# P_ytka.net
KiCad netlist of a schematic drawn in EAGLE
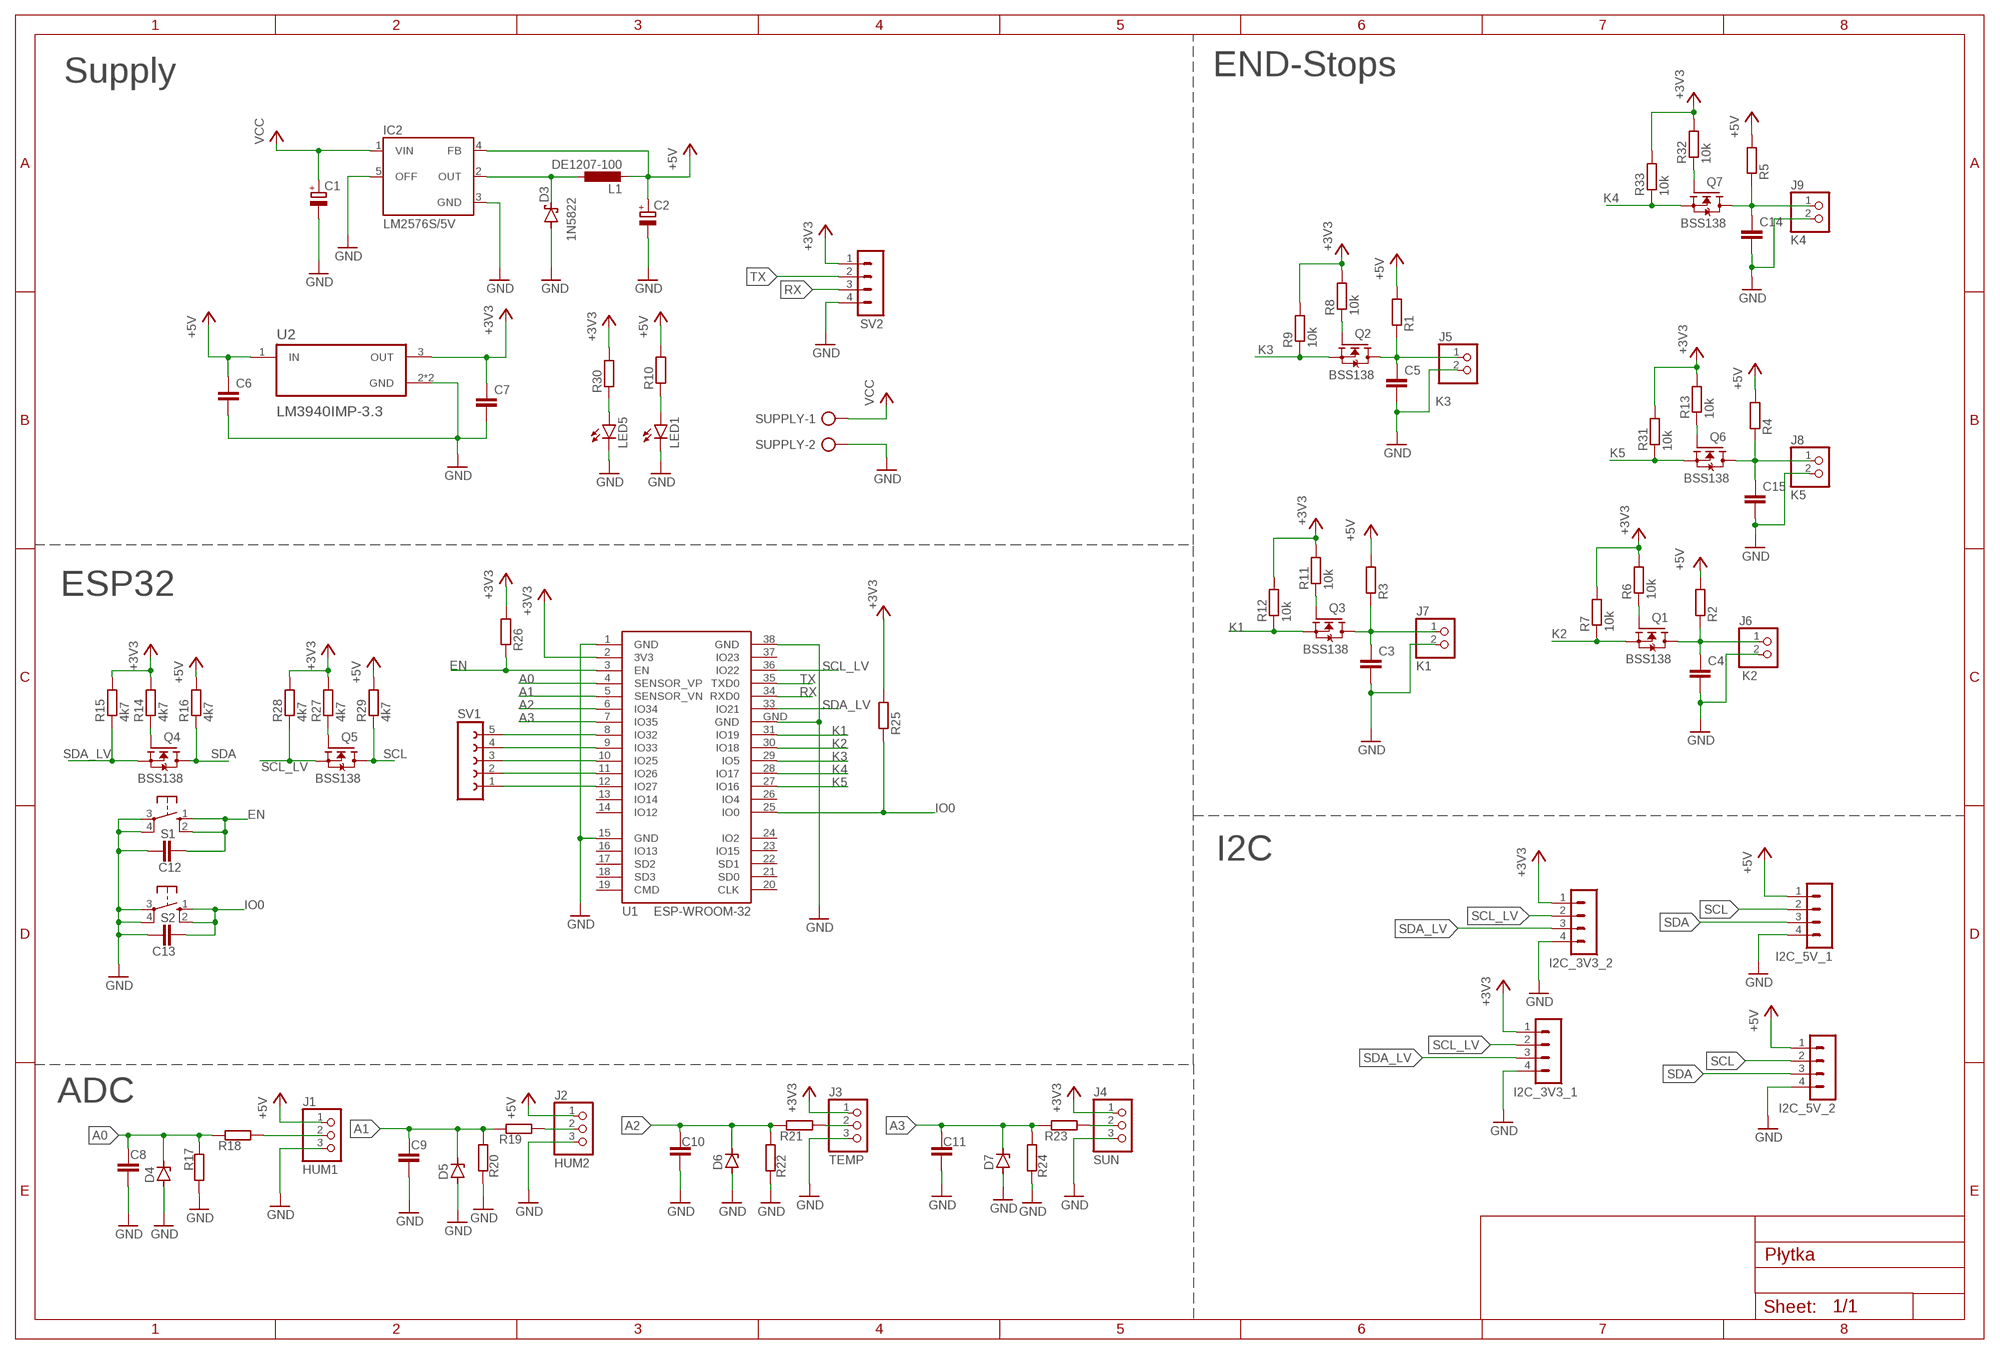
[diagram p0: schematic, sheet 1]

(export (version "E")
  (design (tool "Eeschema 10.0.6"))
  (components
    (comp (ref "C1")
      (value "CPOL-EUE2.5-6")
      (footprint "eagle-import:E2,5-6")
      (libsource (lib "eagle-import") (part "CPOL-EUE2.5-6"))
    )
    (comp (ref "C2")
      (value "CPOL-EUE3.5-8")
      (footprint "eagle-import:E3,5-8")
      (libsource (lib "eagle-import") (part "CPOL-EUE3.5-8"))
    )
    (comp (ref "C3")
      (value "C-EUC0805K")
      (footprint "eagle-import:C0805K")
      (libsource (lib "eagle-import") (part "C-EUC0805K"))
    )
    (comp (ref "C4")
      (value "C-EUC0805K")
      (footprint "eagle-import:C0805K")
      (libsource (lib "eagle-import") (part "C-EUC0805K"))
    )
    (comp (ref "C5")
      (value "C-EUC0805K")
      (footprint "eagle-import:C0805K")
      (libsource (lib "eagle-import") (part "C-EUC0805K"))
    )
    (comp (ref "C6")
      (value "C-EUC0805K")
      (footprint "eagle-import:C0805K")
      (libsource (lib "eagle-import") (part "C-EUC0805K"))
    )
    (comp (ref "C7")
      (value "C-EUC0805K")
      (footprint "eagle-import:C0805K")
      (libsource (lib "eagle-import") (part "C-EUC0805K"))
    )
    (comp (ref "C8")
      (value "C-EUC0805K")
      (footprint "eagle-import:C0805K")
      (libsource (lib "eagle-import") (part "C-EUC0805K"))
    )
    (comp (ref "C9")
      (value "C-EUC0805K")
      (footprint "eagle-import:C0805K")
      (libsource (lib "eagle-import") (part "C-EUC0805K"))
    )
    (comp (ref "C10")
      (value "C-EUC0805K")
      (footprint "eagle-import:C0805K")
      (libsource (lib "eagle-import") (part "C-EUC0805K"))
    )
    (comp (ref "C11")
      (value "C-EUC0805K")
      (footprint "eagle-import:C0805K")
      (libsource (lib "eagle-import") (part "C-EUC0805K"))
    )
    (comp (ref "C12")
      (value "C-EUC0805K")
      (footprint "eagle-import:C0805K")
      (libsource (lib "eagle-import") (part "C-EUC0805K"))
    )
    (comp (ref "C13")
      (value "C-EUC0805K")
      (footprint "eagle-import:C0805K")
      (libsource (lib "eagle-import") (part "C-EUC0805K"))
    )
    (comp (ref "C14")
      (value "C-EUC0805K")
      (footprint "eagle-import:C0805K")
      (libsource (lib "eagle-import") (part "C-EUC0805K"))
    )
    (comp (ref "C15")
      (value "C-EUC0805K")
      (footprint "eagle-import:C0805K")
      (libsource (lib "eagle-import") (part "C-EUC0805K"))
    )
    (comp (ref "D3")
      (value "1N5822")
      (footprint "eagle-import:C4111-15")
      (libsource (lib "eagle-import") (part "1N5908"))
    )
    (comp (ref "D4")
      (value "ZENER-DIODESOD80C")
      (footprint "eagle-import:SOD80C")
      (libsource (lib "eagle-import") (part "ZENER-DIODESOD80C"))
    )
    (comp (ref "D5")
      (value "ZENER-DIODESOD80C")
      (footprint "eagle-import:SOD80C")
      (libsource (lib "eagle-import") (part "ZENER-DIODESOD80C"))
    )
    (comp (ref "D6")
      (value "ZENER-DIODESOD80C")
      (footprint "eagle-import:SOD80C")
      (libsource (lib "eagle-import") (part "ZENER-DIODESOD80C"))
    )
    (comp (ref "D7")
      (value "ZENER-DIODESOD80C")
      (footprint "eagle-import:SOD80C")
      (libsource (lib "eagle-import") (part "ZENER-DIODESOD80C"))
    )
    (comp (ref "I2C_3V3_1")
      (value "MA04-1")
      (footprint "eagle-import:MA04-1")
      (libsource (lib "eagle-import") (part "MA04-1"))
    )
    (comp (ref "I2C_3V3_2")
      (value "MA04-1")
      (footprint "eagle-import:MA04-1")
      (libsource (lib "eagle-import") (part "MA04-1"))
    )
    (comp (ref "I2C_5V_1")
      (value "MA04-1")
      (footprint "eagle-import:MA04-1")
      (libsource (lib "eagle-import") (part "MA04-1"))
    )
    (comp (ref "I2C_5V_2")
      (value "MA04-1")
      (footprint "eagle-import:MA04-1")
      (libsource (lib "eagle-import") (part "MA04-1"))
    )
    (comp (ref "IC2")
      (value "LM2576S/5V")
      (footprint "eagle-import:TO220-5")
      (libsource (lib "eagle-import") (part "LM2576T"))
    )
    (comp (ref "J1")
      (value "HUM1")
      (footprint "eagle-import:W_TYPE_2MM_3_N")
      (libsource (lib "eagle-import") (part "WT-2MM-3PINSTRAIGHT"))
    )
    (comp (ref "J2")
      (value "HUM2")
      (footprint "eagle-import:W_TYPE_2MM_3_N")
      (libsource (lib "eagle-import") (part "WT-2MM-3PINSTRAIGHT"))
    )
    (comp (ref "J3")
      (value "TEMP")
      (footprint "eagle-import:W_TYPE_2MM_3_N")
      (libsource (lib "eagle-import") (part "WT-2MM-3PINSTRAIGHT"))
    )
    (comp (ref "J4")
      (value "SUN")
      (footprint "eagle-import:W_TYPE_2MM_3_N")
      (libsource (lib "eagle-import") (part "WT-2MM-3PINSTRAIGHT"))
    )
    (comp (ref "J5")
      (value "K3")
      (footprint "eagle-import:W_TYPE_2MM_2_N")
      (libsource (lib "eagle-import") (part "WT-2MM-2PINSTRAIGHT"))
    )
    (comp (ref "J6")
      (value "K2")
      (footprint "eagle-import:W_TYPE_2MM_2_N")
      (libsource (lib "eagle-import") (part "WT-2MM-2PINSTRAIGHT"))
    )
    (comp (ref "J7")
      (value "K1")
      (footprint "eagle-import:W_TYPE_2MM_2_N")
      (libsource (lib "eagle-import") (part "WT-2MM-2PINSTRAIGHT"))
    )
    (comp (ref "J8")
      (value "K5")
      (footprint "eagle-import:W_TYPE_2MM_2_N")
      (libsource (lib "eagle-import") (part "WT-2MM-2PINSTRAIGHT"))
    )
    (comp (ref "J9")
      (value "K4")
      (footprint "eagle-import:W_TYPE_2MM_2_N")
      (libsource (lib "eagle-import") (part "WT-2MM-2PINSTRAIGHT"))
    )
    (comp (ref "L1")
      (value "DE1207-100")
      (footprint "eagle-import:DE1207")
      (libsource (lib "eagle-import") (part "DE1207-100"))
    )
    (comp (ref "LED1")
      (value "LEDSML0805")
      (footprint "eagle-import:SML0805")
      (libsource (lib "eagle-import") (part "LEDSML0805"))
    )
    (comp (ref "LED5")
      (value "LEDSML0805")
      (footprint "eagle-import:SML0805")
      (libsource (lib "eagle-import") (part "LEDSML0805"))
    )
    (comp (ref "Q1")
      (value "BSS138")
      (footprint "eagle-import:SOT23")
      (fields (field (name "MF") "Fairchild"))
      (libsource (lib "eagle-import") (part "BSS138"))
    )
    (comp (ref "Q2")
      (value "BSS138")
      (footprint "eagle-import:SOT23")
      (fields (field (name "MF") "Fairchild"))
      (libsource (lib "eagle-import") (part "BSS138"))
    )
    (comp (ref "Q3")
      (value "BSS138")
      (footprint "eagle-import:SOT23")
      (fields (field (name "MF") "Fairchild"))
      (libsource (lib "eagle-import") (part "BSS138"))
    )
    (comp (ref "Q4")
      (value "BSS138")
      (footprint "eagle-import:SOT23")
      (fields (field (name "MF") "Fairchild"))
      (libsource (lib "eagle-import") (part "BSS138"))
    )
    (comp (ref "Q5")
      (value "BSS138")
      (footprint "eagle-import:SOT23")
      (fields (field (name "MF") "Fairchild"))
      (libsource (lib "eagle-import") (part "BSS138"))
    )
    (comp (ref "Q6")
      (value "BSS138")
      (footprint "eagle-import:SOT23")
      (fields (field (name "MF") "Fairchild"))
      (libsource (lib "eagle-import") (part "BSS138"))
    )
    (comp (ref "Q7")
      (value "BSS138")
      (footprint "eagle-import:SOT23")
      (fields (field (name "MF") "Fairchild"))
      (libsource (lib "eagle-import") (part "BSS138"))
    )
    (comp (ref "R1")
      (value "R-EU_R0805")
      (footprint "eagle-import:R0805")
      (libsource (lib "eagle-import") (part "R-EU_R0805"))
    )
    (comp (ref "R2")
      (value "R-EU_R0805")
      (footprint "eagle-import:R0805")
      (libsource (lib "eagle-import") (part "R-EU_R0805"))
    )
    (comp (ref "R3")
      (value "R-EU_R0805")
      (footprint "eagle-import:R0805")
      (libsource (lib "eagle-import") (part "R-EU_R0805"))
    )
    (comp (ref "R4")
      (value "R-EU_R0805")
      (footprint "eagle-import:R0805")
      (libsource (lib "eagle-import") (part "R-EU_R0805"))
    )
    (comp (ref "R5")
      (value "R-EU_R0805")
      (footprint "eagle-import:R0805")
      (libsource (lib "eagle-import") (part "R-EU_R0805"))
    )
    (comp (ref "R6")
      (value "10k")
      (footprint "eagle-import:R0805")
      (libsource (lib "eagle-import") (part "R-EU_R0805"))
    )
    (comp (ref "R7")
      (value "10k")
      (footprint "eagle-import:R0805")
      (libsource (lib "eagle-import") (part "R-EU_R0805"))
    )
    (comp (ref "R8")
      (value "10k")
      (footprint "eagle-import:R0805")
      (libsource (lib "eagle-import") (part "R-EU_R0805"))
    )
    (comp (ref "R9")
      (value "10k")
      (footprint "eagle-import:R0805")
      (libsource (lib "eagle-import") (part "R-EU_R0805"))
    )
    (comp (ref "R10")
      (value "R-EU_R0805")
      (footprint "eagle-import:R0805")
      (libsource (lib "eagle-import") (part "R-EU_R0805"))
    )
    (comp (ref "R11")
      (value "10k")
      (footprint "eagle-import:R0805")
      (libsource (lib "eagle-import") (part "R-EU_R0805"))
    )
    (comp (ref "R12")
      (value "10k")
      (footprint "eagle-import:R0805")
      (libsource (lib "eagle-import") (part "R-EU_R0805"))
    )
    (comp (ref "R13")
      (value "10k")
      (footprint "eagle-import:R0805")
      (libsource (lib "eagle-import") (part "R-EU_R0805"))
    )
    (comp (ref "R14")
      (value "4k7")
      (footprint "eagle-import:R0805")
      (libsource (lib "eagle-import") (part "R-EU_R0805"))
    )
    (comp (ref "R15")
      (value "4k7")
      (footprint "eagle-import:R0805")
      (libsource (lib "eagle-import") (part "R-EU_R0805"))
    )
    (comp (ref "R16")
      (value "4k7")
      (footprint "eagle-import:R0805")
      (libsource (lib "eagle-import") (part "R-EU_R0805"))
    )
    (comp (ref "R17")
      (value "R-EU_R0805")
      (footprint "eagle-import:R0805")
      (libsource (lib "eagle-import") (part "R-EU_R0805"))
    )
    (comp (ref "R18")
      (value "R-EU_R0805")
      (footprint "eagle-import:R0805")
      (libsource (lib "eagle-import") (part "R-EU_R0805"))
    )
    (comp (ref "R19")
      (value "R-EU_R0805")
      (footprint "eagle-import:R0805")
      (libsource (lib "eagle-import") (part "R-EU_R0805"))
    )
    (comp (ref "R20")
      (value "R-EU_R0805")
      (footprint "eagle-import:R0805")
      (libsource (lib "eagle-import") (part "R-EU_R0805"))
    )
    (comp (ref "R21")
      (value "R-EU_R0805")
      (footprint "eagle-import:R0805")
      (libsource (lib "eagle-import") (part "R-EU_R0805"))
    )
    (comp (ref "R22")
      (value "R-EU_R0805")
      (footprint "eagle-import:R0805")
      (libsource (lib "eagle-import") (part "R-EU_R0805"))
    )
    (comp (ref "R23")
      (value "R-EU_R0805")
      (footprint "eagle-import:R0805")
      (libsource (lib "eagle-import") (part "R-EU_R0805"))
    )
    (comp (ref "R24")
      (value "R-EU_R0805")
      (footprint "eagle-import:R0805")
      (libsource (lib "eagle-import") (part "R-EU_R0805"))
    )
    (comp (ref "R25")
      (value "R-EU_R0805")
      (footprint "eagle-import:R0805")
      (libsource (lib "eagle-import") (part "R-EU_R0805"))
    )
    (comp (ref "R26")
      (value "R-EU_R0805")
      (footprint "eagle-import:R0805")
      (libsource (lib "eagle-import") (part "R-EU_R0805"))
    )
    (comp (ref "R27")
      (value "4k7")
      (footprint "eagle-import:R0805")
      (libsource (lib "eagle-import") (part "R-EU_R0805"))
    )
    (comp (ref "R28")
      (value "4k7")
      (footprint "eagle-import:R0805")
      (libsource (lib "eagle-import") (part "R-EU_R0805"))
    )
    (comp (ref "R29")
      (value "4k7")
      (footprint "eagle-import:R0805")
      (libsource (lib "eagle-import") (part "R-EU_R0805"))
    )
    (comp (ref "R30")
      (value "R-EU_R0805")
      (footprint "eagle-import:R0805")
      (libsource (lib "eagle-import") (part "R-EU_R0805"))
    )
    (comp (ref "R31")
      (value "10k")
      (footprint "eagle-import:R0805")
      (libsource (lib "eagle-import") (part "R-EU_R0805"))
    )
    (comp (ref "R32")
      (value "10k")
      (footprint "eagle-import:R0805")
      (libsource (lib "eagle-import") (part "R-EU_R0805"))
    )
    (comp (ref "R33")
      (value "10k")
      (footprint "eagle-import:R0805")
      (libsource (lib "eagle-import") (part "R-EU_R0805"))
    )
    (comp (ref "S1")
      (value "10-XX")
      (footprint "eagle-import:B3F-10XX")
      (fields (field (name "MPN") "B3F-1000"))
      (libsource (lib "eagle-import") (part "10-XX"))
    )
    (comp (ref "S2")
      (value "10-XX")
      (footprint "eagle-import:B3F-10XX")
      (fields (field (name "MPN") "B3F-1000"))
      (libsource (lib "eagle-import") (part "10-XX"))
    )
    (comp (ref "SUPPLY")
      (value "AK500/2-H")
      (footprint "eagle-import:AK500_2-H")
      (libsource (lib "eagle-import") (part "AK500/2-H"))
    )
    (comp (ref "SV1")
      (value "FE05-1")
      (footprint "eagle-import:FE05-1")
      (libsource (lib "eagle-import") (part "FE05-1"))
    )
    (comp (ref "SV2")
      (value "MA04-1")
      (footprint "eagle-import:MA04-1")
      (libsource (lib "eagle-import") (part "MA04-1"))
    )
    (comp (ref "U1")
      (value "ESP-WROOM-32")
      (footprint "eagle-import:ESP-WROOM-32")
      (libsource (lib "eagle-import") (part "ESP-WROOM-32"))
    )
    (comp (ref "U2")
      (value "LM3940IMP-3.3")
      (footprint "eagle-import:SOT230P700X180-4N")
      (fields (field (name "MF") "Texas Instruments"))
      (libsource (lib "eagle-import") (part "LM3940IMP-3.3"))
    )
  )
  (nets
    (net (code "1") (name "+3V3") (class "Default")
      (node (ref "C7") (pin "1") (pinfunction "1_1") (pintype "passive"))
      (node (ref "I2C_3V3_1") (pin "1") (pinfunction "1_1") (pintype "passive"))
      (node (ref "I2C_3V3_2") (pin "1") (pinfunction "1_1") (pintype "passive"))
      (node (ref "J3") (pin "1") (pinfunction "1_1") (pintype "passive"))
      (node (ref "J4") (pin "1") (pinfunction "1_1") (pintype "passive"))
      (node (ref "R11") (pin "2") (pinfunction "2_2") (pintype "passive"))
      (node (ref "R12") (pin "2") (pinfunction "2_2") (pintype "passive"))
      (node (ref "R13") (pin "2") (pinfunction "2_2") (pintype "passive"))
      (node (ref "R14") (pin "2") (pinfunction "2_2") (pintype "passive"))
      (node (ref "R15") (pin "2") (pinfunction "2_2") (pintype "passive"))
      (node (ref "R25") (pin "2") (pinfunction "2_2") (pintype "passive"))
      (node (ref "R26") (pin "2") (pinfunction "2_2") (pintype "passive"))
      (node (ref "R27") (pin "2") (pinfunction "2_2") (pintype "passive"))
      (node (ref "R28") (pin "2") (pinfunction "2_2") (pintype "passive"))
      (node (ref "R30") (pin "2") (pinfunction "2_2") (pintype "passive"))
      (node (ref "R31") (pin "2") (pinfunction "2_2") (pintype "passive"))
      (node (ref "R32") (pin "2") (pinfunction "2_2") (pintype "passive"))
      (node (ref "R33") (pin "2") (pinfunction "2_2") (pintype "passive"))
      (node (ref "R6") (pin "2") (pinfunction "2_2") (pintype "passive"))
      (node (ref "R7") (pin "2") (pinfunction "2_2") (pintype "passive"))
      (node (ref "R8") (pin "2") (pinfunction "2_2") (pintype "passive"))
      (node (ref "R9") (pin "2") (pinfunction "2_2") (pintype "passive"))
      (node (ref "SV2") (pin "1") (pinfunction "1_1") (pintype "passive"))
      (node (ref "U1") (pin "2") (pinfunction "3V3_2") (pintype "power_in"))
      (node (ref "U2") (pin "3") (pinfunction "OUT_3") (pintype "output"))
    )
    (net (code "2") (name "+5V") (class "Default")
      (node (ref "C2") (pin "+") (pinfunction "+_+") (pintype "passive"))
      (node (ref "C6") (pin "1") (pinfunction "1_1") (pintype "passive"))
      (node (ref "I2C_5V_1") (pin "1") (pinfunction "1_1") (pintype "passive"))
      (node (ref "I2C_5V_2") (pin "1") (pinfunction "1_1") (pintype "passive"))
      (node (ref "IC2") (pin "4") (pinfunction "FB_4") (pintype "input"))
      (node (ref "J1") (pin "1") (pinfunction "1_1") (pintype "passive"))
      (node (ref "J2") (pin "1") (pinfunction "1_1") (pintype "passive"))
      (node (ref "L1") (pin "2") (pinfunction "2_2") (pintype "passive"))
      (node (ref "R1") (pin "2") (pinfunction "2_2") (pintype "passive"))
      (node (ref "R10") (pin "2") (pinfunction "2_2") (pintype "passive"))
      (node (ref "R16") (pin "2") (pinfunction "2_2") (pintype "passive"))
      (node (ref "R2") (pin "2") (pinfunction "2_2") (pintype "passive"))
      (node (ref "R29") (pin "2") (pinfunction "2_2") (pintype "passive"))
      (node (ref "R3") (pin "2") (pinfunction "2_2") (pintype "passive"))
      (node (ref "R4") (pin "2") (pinfunction "2_2") (pintype "passive"))
      (node (ref "R5") (pin "2") (pinfunction "2_2") (pintype "passive"))
      (node (ref "U2") (pin "1") (pinfunction "IN_1") (pintype "input"))
    )
    (net (code "3") (name "/EN") (class "Default")
      (node (ref "C12") (pin "2") (pinfunction "2_2") (pintype "passive"))
      (node (ref "R26") (pin "1") (pinfunction "1_1") (pintype "passive"))
      (node (ref "S1") (pin "1") (pinfunction "S_1") (pintype "passive"))
      (node (ref "S1") (pin "2") (pinfunction "S1_2") (pintype "passive"))
      (node (ref "U1") (pin "3") (pinfunction "EN_3") (pintype "input"))
    )
    (net (code "4") (name "/IO0") (class "Default")
      (node (ref "C13") (pin "2") (pinfunction "2_2") (pintype "passive"))
      (node (ref "R25") (pin "1") (pinfunction "1_1") (pintype "passive"))
      (node (ref "S2") (pin "1") (pinfunction "S_1") (pintype "passive"))
      (node (ref "S2") (pin "2") (pinfunction "S1_2") (pintype "passive"))
      (node (ref "U1") (pin "25") (pinfunction "IO0_25") (pintype "bidirectional"))
    )
    (net (code "5") (name "/K1") (class "Default")
      (node (ref "Q3") (pin "2") (pinfunction "S_2") (pintype "passive"))
      (node (ref "R12") (pin "1") (pinfunction "1_1") (pintype "passive"))
      (node (ref "U1") (pin "31") (pinfunction "IO19_31") (pintype "bidirectional"))
    )
    (net (code "6") (name "/K2") (class "Default")
      (node (ref "Q1") (pin "2") (pinfunction "S_2") (pintype "passive"))
      (node (ref "R7") (pin "1") (pinfunction "1_1") (pintype "passive"))
      (node (ref "U1") (pin "30") (pinfunction "IO18_30") (pintype "bidirectional"))
    )
    (net (code "7") (name "/K3") (class "Default")
      (node (ref "Q2") (pin "2") (pinfunction "S_2") (pintype "passive"))
      (node (ref "R9") (pin "1") (pinfunction "1_1") (pintype "passive"))
      (node (ref "U1") (pin "29") (pinfunction "IO5_29") (pintype "bidirectional"))
    )
    (net (code "8") (name "/K4") (class "Default")
      (node (ref "Q7") (pin "2") (pinfunction "S_2") (pintype "passive"))
      (node (ref "R33") (pin "1") (pinfunction "1_1") (pintype "passive"))
      (node (ref "U1") (pin "28") (pinfunction "IO17_28") (pintype "bidirectional"))
    )
    (net (code "9") (name "/K5") (class "Default")
      (node (ref "Q6") (pin "2") (pinfunction "S_2") (pintype "passive"))
      (node (ref "R31") (pin "1") (pinfunction "1_1") (pintype "passive"))
      (node (ref "U1") (pin "27") (pinfunction "IO16_27") (pintype "bidirectional"))
    )
    (net (code "10") (name "A0") (class "Default")
      (node (ref "C8") (pin "1") (pinfunction "1_1") (pintype "passive"))
      (node (ref "D4") (pin "C") (pinfunction "C_C") (pintype "passive"))
      (node (ref "R17") (pin "2") (pinfunction "2_2") (pintype "passive"))
      (node (ref "R18") (pin "2") (pinfunction "2_2") (pintype "passive"))
      (node (ref "U1") (pin "4") (pinfunction "SENSOR_VP_4") (pintype "bidirectional"))
    )
    (net (code "11") (name "A1") (class "Default")
      (node (ref "C9") (pin "1") (pinfunction "1_1") (pintype "passive"))
      (node (ref "D5") (pin "C") (pinfunction "C_C") (pintype "passive"))
      (node (ref "R19") (pin "2") (pinfunction "2_2") (pintype "passive"))
      (node (ref "R20") (pin "1") (pinfunction "1_1") (pintype "passive"))
      (node (ref "U1") (pin "5") (pinfunction "SENSOR_VN_5") (pintype "bidirectional"))
    )
    (net (code "12") (name "A2") (class "Default")
      (node (ref "C10") (pin "1") (pinfunction "1_1") (pintype "passive"))
      (node (ref "D6") (pin "C") (pinfunction "C_C") (pintype "passive"))
      (node (ref "R21") (pin "2") (pinfunction "2_2") (pintype "passive"))
      (node (ref "R22") (pin "1") (pinfunction "1_1") (pintype "passive"))
      (node (ref "U1") (pin "6") (pinfunction "IO34_6") (pintype "bidirectional"))
    )
    (net (code "13") (name "A3") (class "Default")
      (node (ref "C11") (pin "1") (pinfunction "1_1") (pintype "passive"))
      (node (ref "D7") (pin "C") (pinfunction "C_C") (pintype "passive"))
      (node (ref "R23") (pin "2") (pinfunction "2_2") (pintype "passive"))
      (node (ref "R24") (pin "1") (pinfunction "1_1") (pintype "passive"))
      (node (ref "U1") (pin "7") (pinfunction "IO35_7") (pintype "bidirectional"))
    )
    (net (code "14") (name "GND") (class "Default")
      (node (ref "C1") (pin "-") (pinfunction "-_-") (pintype "passive"))
      (node (ref "C10") (pin "2") (pinfunction "2_2") (pintype "passive"))
      (node (ref "C11") (pin "2") (pinfunction "2_2") (pintype "passive"))
      (node (ref "C12") (pin "1") (pinfunction "1_1") (pintype "passive"))
      (node (ref "C13") (pin "1") (pinfunction "1_1") (pintype "passive"))
      (node (ref "C14") (pin "2") (pinfunction "2_2") (pintype "passive"))
      (node (ref "C15") (pin "2") (pinfunction "2_2") (pintype "passive"))
      (node (ref "C2") (pin "-") (pinfunction "-_-") (pintype "passive"))
      (node (ref "C3") (pin "2") (pinfunction "2_2") (pintype "passive"))
      (node (ref "C4") (pin "2") (pinfunction "2_2") (pintype "passive"))
      (node (ref "C5") (pin "2") (pinfunction "2_2") (pintype "passive"))
      (node (ref "C6") (pin "2") (pinfunction "2_2") (pintype "passive"))
      (node (ref "C7") (pin "2") (pinfunction "2_2") (pintype "passive"))
      (node (ref "C8") (pin "2") (pinfunction "2_2") (pintype "passive"))
      (node (ref "C9") (pin "2") (pinfunction "2_2") (pintype "passive"))
      (node (ref "D3") (pin "A") (pinfunction "A_A") (pintype "passive"))
      (node (ref "D4") (pin "A") (pinfunction "A_A") (pintype "passive"))
      (node (ref "D5") (pin "A") (pinfunction "A_A") (pintype "passive"))
      (node (ref "D6") (pin "A") (pinfunction "A_A") (pintype "passive"))
      (node (ref "D7") (pin "A") (pinfunction "A_A") (pintype "passive"))
      (node (ref "I2C_3V3_1") (pin "4") (pinfunction "4_4") (pintype "passive"))
      (node (ref "I2C_3V3_2") (pin "4") (pinfunction "4_4") (pintype "passive"))
      (node (ref "I2C_5V_1") (pin "4") (pinfunction "4_4") (pintype "passive"))
      (node (ref "I2C_5V_2") (pin "4") (pinfunction "4_4") (pintype "passive"))
      (node (ref "IC2") (pin "3") (pinfunction "GND_3") (pintype "power_in"))
      (node (ref "IC2") (pin "5") (pinfunction "OFF_5") (pintype "input"))
      (node (ref "J1") (pin "3") (pinfunction "3_3") (pintype "passive"))
      (node (ref "J2") (pin "3") (pinfunction "3_3") (pintype "passive"))
      (node (ref "J3") (pin "3") (pinfunction "3_3") (pintype "passive"))
      (node (ref "J4") (pin "3") (pinfunction "3_3") (pintype "passive"))
      (node (ref "J5") (pin "2") (pinfunction "2_2") (pintype "passive"))
      (node (ref "J6") (pin "2") (pinfunction "2_2") (pintype "passive"))
      (node (ref "J7") (pin "2") (pinfunction "2_2") (pintype "passive"))
      (node (ref "J8") (pin "2") (pinfunction "2_2") (pintype "passive"))
      (node (ref "J9") (pin "2") (pinfunction "2_2") (pintype "passive"))
      (node (ref "LED1") (pin "C") (pinfunction "C_C") (pintype "passive"))
      (node (ref "LED5") (pin "C") (pinfunction "C_C") (pintype "passive"))
      (node (ref "R17") (pin "1") (pinfunction "1_1") (pintype "passive"))
      (node (ref "R20") (pin "2") (pinfunction "2_2") (pintype "passive"))
      (node (ref "R22") (pin "2") (pinfunction "2_2") (pintype "passive"))
      (node (ref "R24") (pin "2") (pinfunction "2_2") (pintype "passive"))
      (node (ref "S1") (pin "3") (pinfunction "P_3") (pintype "passive"))
      (node (ref "S1") (pin "4") (pinfunction "P1_4") (pintype "passive"))
      (node (ref "S2") (pin "3") (pinfunction "P_3") (pintype "passive"))
      (node (ref "S2") (pin "4") (pinfunction "P1_4") (pintype "passive"))
      (node (ref "SUPPLY") (pin "2") (pinfunction "KL_2") (pintype "passive"))
      (node (ref "SV2") (pin "4") (pinfunction "4_4") (pintype "passive"))
      (node (ref "U1") (pin "1") (pinfunction "GND_1") (pintype "power_in"))
      (node (ref "U1") (pin "15") (pinfunction "GND_15") (pintype "power_in"))
      (node (ref "U1") (pin "38") (pinfunction "GND_38") (pintype "power_in"))
      (node (ref "U1") (pin "GND") (pinfunction "GND_GND") (pintype "power_in"))
      (node (ref "U2") (pin "2") (pinfunction "GND_2") (pintype "power_in"))
      (node (ref "U2") (pin "4") (pinfunction "GND_4") (pintype "power_in"))
    )
    (net (code "15") (name "Net-(IC2-OUT)") (class "Default")
      (node (ref "D3") (pin "C") (pinfunction "C_C") (pintype "passive"))
      (node (ref "IC2") (pin "2") (pinfunction "OUT_2") (pintype "output"))
      (node (ref "L1") (pin "1") (pinfunction "1_1") (pintype "passive"))
    )
    (net (code "16") (name "Net-(J1-Pad2)") (class "Default")
      (node (ref "J1") (pin "2") (pinfunction "2_2") (pintype "passive"))
      (node (ref "R18") (pin "1") (pinfunction "1_1") (pintype "passive"))
    )
    (net (code "17") (name "Net-(J2-Pad2)") (class "Default")
      (node (ref "J2") (pin "2") (pinfunction "2_2") (pintype "passive"))
      (node (ref "R19") (pin "1") (pinfunction "1_1") (pintype "passive"))
    )
    (net (code "18") (name "Net-(J3-Pad2)") (class "Default")
      (node (ref "J3") (pin "2") (pinfunction "2_2") (pintype "passive"))
      (node (ref "R21") (pin "1") (pinfunction "1_1") (pintype "passive"))
    )
    (net (code "19") (name "Net-(J4-Pad2)") (class "Default")
      (node (ref "J4") (pin "2") (pinfunction "2_2") (pintype "passive"))
      (node (ref "R23") (pin "1") (pinfunction "1_1") (pintype "passive"))
    )
    (net (code "20") (name "Net-(LED1-PadA)") (class "Default")
      (node (ref "LED1") (pin "A") (pinfunction "A_A") (pintype "passive"))
      (node (ref "R10") (pin "1") (pinfunction "1_1") (pintype "passive"))
    )
    (net (code "21") (name "Net-(LED5-PadA)") (class "Default")
      (node (ref "LED5") (pin "A") (pinfunction "A_A") (pintype "passive"))
      (node (ref "R30") (pin "1") (pinfunction "1_1") (pintype "passive"))
    )
    (net (code "22") (name "Net-(Q1-D)") (class "Default")
      (node (ref "C4") (pin "1") (pinfunction "1_1") (pintype "passive"))
      (node (ref "J6") (pin "1") (pinfunction "1_1") (pintype "passive"))
      (node (ref "Q1") (pin "3") (pinfunction "D_3") (pintype "passive"))
      (node (ref "R2") (pin "1") (pinfunction "1_1") (pintype "passive"))
    )
    (net (code "23") (name "Net-(Q1-G)") (class "Default")
      (node (ref "Q1") (pin "1") (pinfunction "G_1") (pintype "passive"))
      (node (ref "R6") (pin "1") (pinfunction "1_1") (pintype "passive"))
    )
    (net (code "24") (name "Net-(Q2-D)") (class "Default")
      (node (ref "C5") (pin "1") (pinfunction "1_1") (pintype "passive"))
      (node (ref "J5") (pin "1") (pinfunction "1_1") (pintype "passive"))
      (node (ref "Q2") (pin "3") (pinfunction "D_3") (pintype "passive"))
      (node (ref "R1") (pin "1") (pinfunction "1_1") (pintype "passive"))
    )
    (net (code "25") (name "Net-(Q2-G)") (class "Default")
      (node (ref "Q2") (pin "1") (pinfunction "G_1") (pintype "passive"))
      (node (ref "R8") (pin "1") (pinfunction "1_1") (pintype "passive"))
    )
    (net (code "26") (name "Net-(Q3-D)") (class "Default")
      (node (ref "C3") (pin "1") (pinfunction "1_1") (pintype "passive"))
      (node (ref "J7") (pin "1") (pinfunction "1_1") (pintype "passive"))
      (node (ref "Q3") (pin "3") (pinfunction "D_3") (pintype "passive"))
      (node (ref "R3") (pin "1") (pinfunction "1_1") (pintype "passive"))
    )
    (net (code "27") (name "Net-(Q3-G)") (class "Default")
      (node (ref "Q3") (pin "1") (pinfunction "G_1") (pintype "passive"))
      (node (ref "R11") (pin "1") (pinfunction "1_1") (pintype "passive"))
    )
    (net (code "28") (name "Net-(Q4-G)") (class "Default")
      (node (ref "Q4") (pin "1") (pinfunction "G_1") (pintype "passive"))
      (node (ref "R14") (pin "1") (pinfunction "1_1") (pintype "passive"))
    )
    (net (code "29") (name "Net-(Q5-G)") (class "Default")
      (node (ref "Q5") (pin "1") (pinfunction "G_1") (pintype "passive"))
      (node (ref "R27") (pin "1") (pinfunction "1_1") (pintype "passive"))
    )
    (net (code "30") (name "Net-(Q6-D)") (class "Default")
      (node (ref "C15") (pin "1") (pinfunction "1_1") (pintype "passive"))
      (node (ref "J8") (pin "1") (pinfunction "1_1") (pintype "passive"))
      (node (ref "Q6") (pin "3") (pinfunction "D_3") (pintype "passive"))
      (node (ref "R4") (pin "1") (pinfunction "1_1") (pintype "passive"))
    )
    (net (code "31") (name "Net-(Q6-G)") (class "Default")
      (node (ref "Q6") (pin "1") (pinfunction "G_1") (pintype "passive"))
      (node (ref "R13") (pin "1") (pinfunction "1_1") (pintype "passive"))
    )
    (net (code "32") (name "Net-(Q7-D)") (class "Default")
      (node (ref "C14") (pin "1") (pinfunction "1_1") (pintype "passive"))
      (node (ref "J9") (pin "1") (pinfunction "1_1") (pintype "passive"))
      (node (ref "Q7") (pin "3") (pinfunction "D_3") (pintype "passive"))
      (node (ref "R5") (pin "1") (pinfunction "1_1") (pintype "passive"))
    )
    (net (code "33") (name "Net-(Q7-G)") (class "Default")
      (node (ref "Q7") (pin "1") (pinfunction "G_1") (pintype "passive"))
      (node (ref "R32") (pin "1") (pinfunction "1_1") (pintype "passive"))
    )
    (net (code "34") (name "Net-(U1-IO25)") (class "Default")
      (node (ref "SV1") (pin "3") (pinfunction "3_3") (pintype "passive"))
      (node (ref "U1") (pin "10") (pinfunction "IO25_10") (pintype "bidirectional"))
    )
    (net (code "35") (name "Net-(U1-IO26)") (class "Default")
      (node (ref "SV1") (pin "2") (pinfunction "2_2") (pintype "passive"))
      (node (ref "U1") (pin "11") (pinfunction "IO26_11") (pintype "bidirectional"))
    )
    (net (code "36") (name "Net-(U1-IO27)") (class "Default")
      (node (ref "SV1") (pin "1") (pinfunction "1_1") (pintype "passive"))
      (node (ref "U1") (pin "12") (pinfunction "IO27_12") (pintype "bidirectional"))
    )
    (net (code "37") (name "Net-(U1-IO32)") (class "Default")
      (node (ref "SV1") (pin "5") (pinfunction "5_5") (pintype "passive"))
      (node (ref "U1") (pin "8") (pinfunction "IO32_8") (pintype "bidirectional"))
    )
    (net (code "38") (name "Net-(U1-IO33)") (class "Default")
      (node (ref "SV1") (pin "4") (pinfunction "4_4") (pintype "passive"))
      (node (ref "U1") (pin "9") (pinfunction "IO33_9") (pintype "bidirectional"))
    )
    (net (code "39") (name "RX") (class "Default")
      (node (ref "SV2") (pin "3") (pinfunction "3_3") (pintype "passive"))
      (node (ref "U1") (pin "34") (pinfunction "RXD0_34") (pintype "bidirectional"))
    )
    (net (code "40") (name "SCL") (class "Default")
      (node (ref "I2C_5V_1") (pin "2") (pinfunction "2_2") (pintype "passive"))
      (node (ref "I2C_5V_2") (pin "2") (pinfunction "2_2") (pintype "passive"))
      (node (ref "Q5") (pin "3") (pinfunction "D_3") (pintype "passive"))
      (node (ref "R29") (pin "1") (pinfunction "1_1") (pintype "passive"))
    )
    (net (code "41") (name "SCL_LV") (class "Default")
      (node (ref "I2C_3V3_1") (pin "2") (pinfunction "2_2") (pintype "passive"))
      (node (ref "I2C_3V3_2") (pin "2") (pinfunction "2_2") (pintype "passive"))
      (node (ref "Q5") (pin "2") (pinfunction "S_2") (pintype "passive"))
      (node (ref "R28") (pin "1") (pinfunction "1_1") (pintype "passive"))
      (node (ref "U1") (pin "36") (pinfunction "IO22_36") (pintype "bidirectional"))
    )
    (net (code "42") (name "SDA") (class "Default")
      (node (ref "I2C_5V_1") (pin "3") (pinfunction "3_3") (pintype "passive"))
      (node (ref "I2C_5V_2") (pin "3") (pinfunction "3_3") (pintype "passive"))
      (node (ref "Q4") (pin "3") (pinfunction "D_3") (pintype "passive"))
      (node (ref "R16") (pin "1") (pinfunction "1_1") (pintype "passive"))
    )
    (net (code "43") (name "SDA_LV") (class "Default")
      (node (ref "I2C_3V3_1") (pin "3") (pinfunction "3_3") (pintype "passive"))
      (node (ref "I2C_3V3_2") (pin "3") (pinfunction "3_3") (pintype "passive"))
      (node (ref "Q4") (pin "2") (pinfunction "S_2") (pintype "passive"))
      (node (ref "R15") (pin "1") (pinfunction "1_1") (pintype "passive"))
      (node (ref "U1") (pin "33") (pinfunction "IO21_33") (pintype "bidirectional"))
    )
    (net (code "44") (name "TX") (class "Default")
      (node (ref "SV2") (pin "2") (pinfunction "2_2") (pintype "passive"))
      (node (ref "U1") (pin "35") (pinfunction "TXD0_35") (pintype "bidirectional"))
    )
    (net (code "45") (name "VCC") (class "Default")
      (node (ref "C1") (pin "+") (pinfunction "+_+") (pintype "passive"))
      (node (ref "IC2") (pin "1") (pinfunction "VIN_1") (pintype "power_in"))
      (node (ref "SUPPLY") (pin "1") (pinfunction "KL_1") (pintype "passive"))
    )
    (net (code "46") (name "unconnected-(U1-CLK-Pad20)") (class "Default")
      (node (ref "U1") (pin "20") (pinfunction "CLK_20") (pintype "bidirectional"))
    )
    (net (code "47") (name "unconnected-(U1-CMD-Pad19)") (class "Default")
      (node (ref "U1") (pin "19") (pinfunction "CMD_19") (pintype "bidirectional"))
    )
    (net (code "48") (name "unconnected-(U1-IO2-Pad24)") (class "Default")
      (node (ref "U1") (pin "24") (pinfunction "IO2_24") (pintype "bidirectional"))
    )
    (net (code "49") (name "unconnected-(U1-IO4-Pad26)") (class "Default")
      (node (ref "U1") (pin "26") (pinfunction "IO4_26") (pintype "bidirectional"))
    )
    (net (code "50") (name "unconnected-(U1-IO12-Pad14)") (class "Default")
      (node (ref "U1") (pin "14") (pinfunction "IO12_14") (pintype "bidirectional"))
    )
    (net (code "51") (name "unconnected-(U1-IO13-Pad16)") (class "Default")
      (node (ref "U1") (pin "16") (pinfunction "IO13_16") (pintype "bidirectional"))
    )
    (net (code "52") (name "unconnected-(U1-IO14-Pad13)") (class "Default")
      (node (ref "U1") (pin "13") (pinfunction "IO14_13") (pintype "bidirectional"))
    )
    (net (code "53") (name "unconnected-(U1-IO15-Pad23)") (class "Default")
      (node (ref "U1") (pin "23") (pinfunction "IO15_23") (pintype "bidirectional"))
    )
    (net (code "54") (name "unconnected-(U1-IO23-Pad37)") (class "Default")
      (node (ref "U1") (pin "37") (pinfunction "IO23_37") (pintype "bidirectional"))
    )
    (net (code "55") (name "unconnected-(U1-SD0-Pad21)") (class "Default")
      (node (ref "U1") (pin "21") (pinfunction "SD0_21") (pintype "bidirectional"))
    )
    (net (code "56") (name "unconnected-(U1-SD1-Pad22)") (class "Default")
      (node (ref "U1") (pin "22") (pinfunction "SD1_22") (pintype "bidirectional"))
    )
    (net (code "57") (name "unconnected-(U1-SD2-Pad17)") (class "Default")
      (node (ref "U1") (pin "17") (pinfunction "SD2_17") (pintype "bidirectional"))
    )
    (net (code "58") (name "unconnected-(U1-SD3-Pad18)") (class "Default")
      (node (ref "U1") (pin "18") (pinfunction "SD3_18") (pintype "bidirectional"))
    )
  )
)
